# mMicroSD.net
KiCad netlist of a schematic drawn in EAGLE
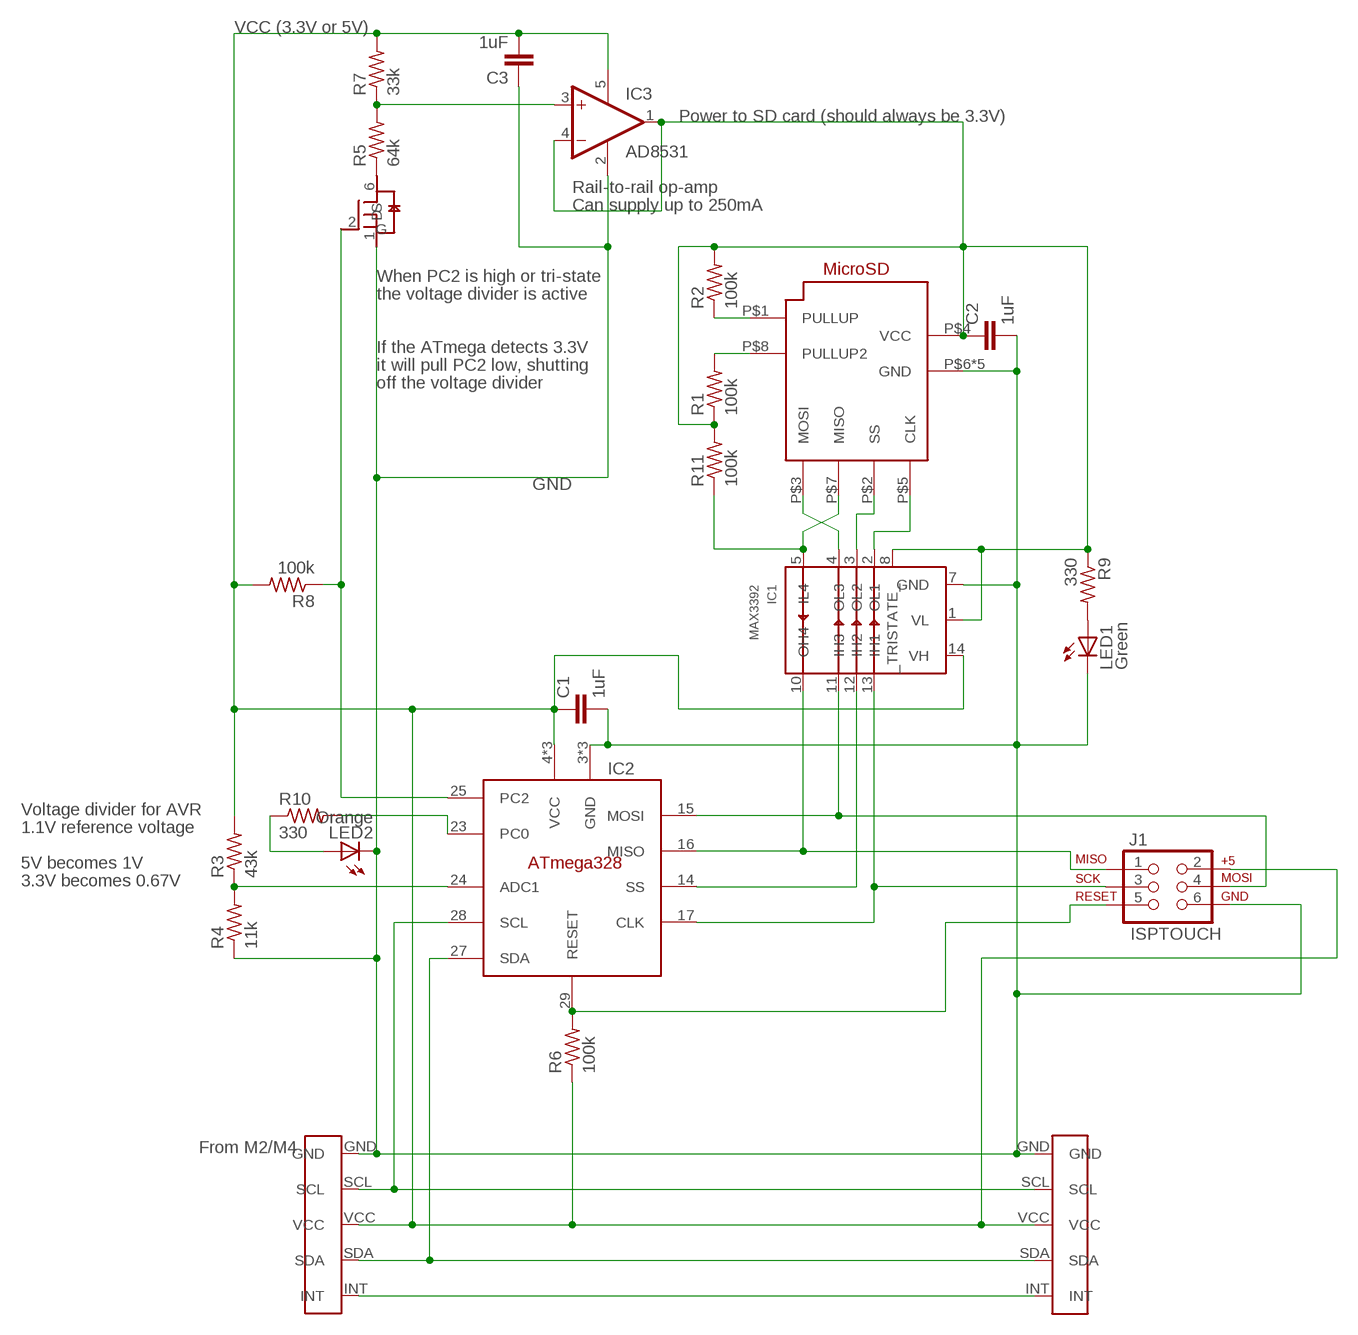
[diagram p0: schematic, sheet 1]

(export (version "E")
  (design (tool "Eeschema 10.0.6"))
  (components
    (comp (ref "C1")
      (value "1uF")
      (footprint "eagle-import:C0603")
      (libsource (lib "eagle-import") (part "C-EUC0603"))
    )
    (comp (ref "C2")
      (value "1uF")
      (footprint "eagle-import:C0603")
      (libsource (lib "eagle-import") (part "C-EUC0603"))
    )
    (comp (ref "C3")
      (value "1uF")
      (footprint "eagle-import:C0603")
      (libsource (lib "eagle-import") (part "C-EUC0603"))
    )
    (comp (ref "IC1")
      (value "MAX3392")
      (footprint "eagle-import:14-TSSOP")
      (libsource (lib "eagle-import") (part "MAX3392"))
    )
    (comp (ref "IC2")
      (value "ATMEGA328")
      (footprint "eagle-import:ATMEGA328")
      (libsource (lib "eagle-import") (part "ATMEGA328"))
    )
    (comp (ref "IC3")
      (value "AD8531")
      (footprint "eagle-import:SOT-23-5")
      (libsource (lib "eagle-import") (part "AD8531"))
    )
    (comp (ref "J1")
      (value "ISPTOUCH")
      (footprint "eagle-import:AVX_9188_6-WAY_SMT")
      (libsource (lib "eagle-import") (part "ISPTOUCH_ADAPTER"))
    )
    (comp (ref "LED1")
      (value "Green")
      (footprint "eagle-import:SML0603")
      (libsource (lib "eagle-import") (part "LEDSML0603"))
    )
    (comp (ref "LED2")
      (value "Orange")
      (footprint "eagle-import:SML0603")
      (libsource (lib "eagle-import") (part "LEDSML0603"))
    )
    (comp (ref "M1")
      (value "NTJD5121N")
      (footprint "eagle-import:SOT-363")
      (libsource (lib "eagle-import") (part "NTJD5121NT1G"))
    )
    (comp (ref "R1")
      (value "100k")
      (footprint "eagle-import:R0603")
      (libsource (lib "eagle-import") (part "R-US_R0603"))
    )
    (comp (ref "R2")
      (value "100k")
      (footprint "eagle-import:R0603")
      (libsource (lib "eagle-import") (part "R-US_R0603"))
    )
    (comp (ref "R3")
      (value "43k")
      (footprint "eagle-import:R0603")
      (libsource (lib "eagle-import") (part "R-US_R0603"))
    )
    (comp (ref "R4")
      (value "11k")
      (footprint "eagle-import:R0603")
      (libsource (lib "eagle-import") (part "R-US_R0603"))
    )
    (comp (ref "R5")
      (value "64k")
      (footprint "eagle-import:R0603")
      (libsource (lib "eagle-import") (part "R-US_R0603"))
    )
    (comp (ref "R6")
      (value "100k")
      (footprint "eagle-import:R0603")
      (libsource (lib "eagle-import") (part "R-US_R0603"))
    )
    (comp (ref "R7")
      (value "33k")
      (footprint "eagle-import:R0603")
      (libsource (lib "eagle-import") (part "R-US_R0603"))
    )
    (comp (ref "R8")
      (value "100k")
      (footprint "eagle-import:R0603")
      (libsource (lib "eagle-import") (part "R-US_R0603"))
    )
    (comp (ref "R9")
      (value "330")
      (footprint "eagle-import:R0603")
      (libsource (lib "eagle-import") (part "R-US_R0603"))
    )
    (comp (ref "R10")
      (value "330")
      (footprint "eagle-import:R0603")
      (libsource (lib "eagle-import") (part "R-US_R0603"))
    )
    (comp (ref "R11")
      (value "100k")
      (footprint "eagle-import:R0603")
      (libsource (lib "eagle-import") (part "R-US_R0603"))
    )
    (comp (ref "SDCONN")
      (value "101-00660-68-6")
      (footprint "eagle-import:101-00660-68-6")
      (libsource (lib "eagle-import") (part "101-00660-68-6"))
    )
    (comp (ref "U$1")
      (value "MBUS_OUT")
      (footprint "eagle-import:MBUS_OUT")
      (libsource (lib "eagle-import") (part "MBUS_OUT"))
    )
    (comp (ref "U$2")
      (value "MBUS_IN")
      (footprint "eagle-import:MBUS_IN")
      (libsource (lib "eagle-import") (part "MBUS_IN"))
    )
  )
  (nets
    (net (code "1") (name "/GND") (class "Default")
      (node (ref "C1") (pin "2") (pinfunction "2_2") (pintype "passive"))
      (node (ref "C2") (pin "2") (pinfunction "2_2") (pintype "passive"))
      (node (ref "C3") (pin "1") (pinfunction "1_1") (pintype "passive"))
      (node (ref "IC1") (pin "7") (pinfunction "GND_7") (pintype "power_in"))
      (node (ref "IC2") (pin "21") (pinfunction "GND_21") (pintype "bidirectional"))
      (node (ref "IC2") (pin "3") (pinfunction "GND_3") (pintype "bidirectional"))
      (node (ref "IC2") (pin "5") (pinfunction "GND_5") (pintype "bidirectional"))
      (node (ref "IC3") (pin "2") (pinfunction "V-_2") (pintype "power_in"))
      (node (ref "J1") (pin "6") (pinfunction "6_6") (pintype "passive"))
      (node (ref "LED1") (pin "C") (pinfunction "C_C") (pintype "passive"))
      (node (ref "LED2") (pin "C") (pinfunction "C_C") (pintype "passive"))
      (node (ref "M1") (pin "1") (pinfunction "S_1") (pintype "bidirectional"))
      (node (ref "R4") (pin "1") (pinfunction "1_1") (pintype "passive"))
      (node (ref "SDCONN") (pin "P$10") (pinfunction "GND_P$10") (pintype "bidirectional"))
      (node (ref "SDCONN") (pin "P$11") (pinfunction "GND_P$11") (pintype "bidirectional"))
      (node (ref "SDCONN") (pin "P$12") (pinfunction "GND_P$12") (pintype "bidirectional"))
      (node (ref "SDCONN") (pin "P$6") (pinfunction "GND_P$6") (pintype "bidirectional"))
      (node (ref "SDCONN") (pin "P$9") (pinfunction "GND_P$9") (pintype "bidirectional"))
      (node (ref "U$1") (pin "GND") (pinfunction "GND_GND") (pintype "bidirectional"))
      (node (ref "U$2") (pin "GND") (pinfunction "GND_GND") (pintype "bidirectional"))
    )
    (net (code "2") (name "Net-(IC1-IH1)") (class "Default")
      (node (ref "IC1") (pin "13") (pinfunction "IH1_13") (pintype "input"))
      (node (ref "IC2") (pin "17") (pinfunction "CLK_17") (pintype "bidirectional"))
      (node (ref "J1") (pin "3") (pinfunction "3_3") (pintype "passive"))
    )
    (net (code "3") (name "Net-(IC1-IH2)") (class "Default")
      (node (ref "IC1") (pin "12") (pinfunction "IH2_12") (pintype "input"))
      (node (ref "IC2") (pin "14") (pinfunction "SS_14") (pintype "bidirectional"))
    )
    (net (code "4") (name "Net-(IC1-IH3)") (class "Default")
      (node (ref "IC1") (pin "11") (pinfunction "IH3_11") (pintype "input"))
      (node (ref "IC2") (pin "15") (pinfunction "MOSI_15") (pintype "bidirectional"))
      (node (ref "J1") (pin "4") (pinfunction "4_4") (pintype "passive"))
    )
    (net (code "5") (name "Net-(IC1-IL4)") (class "Default")
      (node (ref "IC1") (pin "5") (pinfunction "IL4_5") (pintype "input"))
      (node (ref "R11") (pin "1") (pinfunction "1_1") (pintype "passive"))
      (node (ref "SDCONN") (pin "P$7") (pinfunction "MISO_P$7") (pintype "bidirectional"))
    )
    (net (code "6") (name "Net-(IC1-OH4)") (class "Default")
      (node (ref "IC1") (pin "10") (pinfunction "OH4_10") (pintype "output"))
      (node (ref "IC2") (pin "16") (pinfunction "MISO_16") (pintype "bidirectional"))
      (node (ref "J1") (pin "1") (pinfunction "1_1") (pintype "passive"))
    )
    (net (code "7") (name "Net-(IC1-OL1)") (class "Default")
      (node (ref "IC1") (pin "2") (pinfunction "OL1_2") (pintype "output"))
      (node (ref "SDCONN") (pin "P$5") (pinfunction "CLK_P$5") (pintype "bidirectional"))
    )
    (net (code "8") (name "Net-(IC1-OL2)") (class "Default")
      (node (ref "IC1") (pin "3") (pinfunction "OL2_3") (pintype "output"))
      (node (ref "SDCONN") (pin "P$2") (pinfunction "SS_P$2") (pintype "bidirectional"))
    )
    (net (code "9") (name "Net-(IC1-OL3)") (class "Default")
      (node (ref "IC1") (pin "4") (pinfunction "OL3_4") (pintype "output"))
      (node (ref "SDCONN") (pin "P$3") (pinfunction "MOSI_P$3") (pintype "bidirectional"))
    )
    (net (code "10") (name "Net-(IC1-VH)") (class "Default")
      (node (ref "C1") (pin "1") (pinfunction "1_1") (pintype "passive"))
      (node (ref "C3") (pin "2") (pinfunction "2_2") (pintype "passive"))
      (node (ref "IC1") (pin "14") (pinfunction "VH_14") (pintype "power_in"))
      (node (ref "IC2") (pin "18") (pinfunction "VCC_18") (pintype "bidirectional"))
      (node (ref "IC2") (pin "4") (pinfunction "VCC_4") (pintype "bidirectional"))
      (node (ref "IC2") (pin "6") (pinfunction "VCC_6") (pintype "bidirectional"))
      (node (ref "IC3") (pin "5") (pinfunction "V+_5") (pintype "power_in"))
      (node (ref "J1") (pin "2") (pinfunction "2_2") (pintype "passive"))
      (node (ref "R3") (pin "2") (pinfunction "2_2") (pintype "passive"))
      (node (ref "R6") (pin "1") (pinfunction "1_1") (pintype "passive"))
      (node (ref "R7") (pin "2") (pinfunction "2_2") (pintype "passive"))
      (node (ref "R8") (pin "2") (pinfunction "2_2") (pintype "passive"))
      (node (ref "U$1") (pin "VCC") (pinfunction "VCC_VCC") (pintype "bidirectional"))
      (node (ref "U$2") (pin "VCC") (pinfunction "VCC_VCC") (pintype "bidirectional"))
    )
    (net (code "11") (name "Net-(IC1-VL)") (class "Default")
      (node (ref "C2") (pin "1") (pinfunction "1_1") (pintype "passive"))
      (node (ref "IC1") (pin "1") (pinfunction "VL_1") (pintype "power_in"))
      (node (ref "IC1") (pin "8") (pinfunction "_TRISTATE__8") (pintype "input"))
      (node (ref "IC3") (pin "1") (pinfunction "OUT_1") (pintype "output"))
      (node (ref "IC3") (pin "4") (pinfunction "-IN_4") (pintype "input"))
      (node (ref "R1") (pin "1") (pinfunction "1_1") (pintype "passive"))
      (node (ref "R11") (pin "2") (pinfunction "2_2") (pintype "passive"))
      (node (ref "R2") (pin "2") (pinfunction "2_2") (pintype "passive"))
      (node (ref "R9") (pin "1") (pinfunction "1_1") (pintype "passive"))
      (node (ref "SDCONN") (pin "P$4") (pinfunction "VCC_P$4") (pintype "bidirectional"))
    )
    (net (code "12") (name "Net-(IC2-ADC1)") (class "Default")
      (node (ref "IC2") (pin "24") (pinfunction "ADC1_24") (pintype "bidirectional"))
      (node (ref "R3") (pin "1") (pinfunction "1_1") (pintype "passive"))
      (node (ref "R4") (pin "2") (pinfunction "2_2") (pintype "passive"))
    )
    (net (code "13") (name "Net-(IC2-PC0)") (class "Default")
      (node (ref "IC2") (pin "23") (pinfunction "PC0_23") (pintype "bidirectional"))
      (node (ref "R10") (pin "2") (pinfunction "2_2") (pintype "passive"))
    )
    (net (code "14") (name "Net-(IC2-PC2)") (class "Default")
      (node (ref "IC2") (pin "25") (pinfunction "PC2_25") (pintype "bidirectional"))
      (node (ref "M1") (pin "2") (pinfunction "G_2") (pintype "bidirectional"))
      (node (ref "R8") (pin "1") (pinfunction "1_1") (pintype "passive"))
    )
    (net (code "15") (name "Net-(IC2-RESET)") (class "Default")
      (node (ref "IC2") (pin "29") (pinfunction "RESET_29") (pintype "bidirectional"))
      (node (ref "J1") (pin "5") (pinfunction "5_5") (pintype "passive"))
      (node (ref "R6") (pin "2") (pinfunction "2_2") (pintype "passive"))
    )
    (net (code "16") (name "Net-(IC2-SCL)") (class "Default")
      (node (ref "IC2") (pin "28") (pinfunction "SCL_28") (pintype "bidirectional"))
      (node (ref "U$1") (pin "SCL") (pinfunction "SCL_SCL") (pintype "bidirectional"))
      (node (ref "U$2") (pin "SCL") (pinfunction "SCL_SCL") (pintype "bidirectional"))
    )
    (net (code "17") (name "Net-(IC2-SDA)") (class "Default")
      (node (ref "IC2") (pin "27") (pinfunction "SDA_27") (pintype "bidirectional"))
      (node (ref "U$1") (pin "SDA") (pinfunction "SDA_SDA") (pintype "bidirectional"))
      (node (ref "U$2") (pin "SDA") (pinfunction "SDA_SDA") (pintype "bidirectional"))
    )
    (net (code "18") (name "Net-(IC3-+IN)") (class "Default")
      (node (ref "IC3") (pin "3") (pinfunction "+IN_3") (pintype "input"))
      (node (ref "R5") (pin "2") (pinfunction "2_2") (pintype "passive"))
      (node (ref "R7") (pin "1") (pinfunction "1_1") (pintype "passive"))
    )
    (net (code "19") (name "Net-(LED1-PadA)") (class "Default")
      (node (ref "LED1") (pin "A") (pinfunction "A_A") (pintype "passive"))
      (node (ref "R9") (pin "2") (pinfunction "2_2") (pintype "passive"))
    )
    (net (code "20") (name "Net-(LED2-PadA)") (class "Default")
      (node (ref "LED2") (pin "A") (pinfunction "A_A") (pintype "passive"))
      (node (ref "R10") (pin "1") (pinfunction "1_1") (pintype "passive"))
    )
    (net (code "21") (name "Net-(M1A-D)") (class "Default")
      (node (ref "M1") (pin "6") (pinfunction "D_6") (pintype "bidirectional"))
      (node (ref "R5") (pin "1") (pinfunction "1_1") (pintype "passive"))
    )
    (net (code "22") (name "Net-(SDCONN-PULLUP)") (class "Default")
      (node (ref "R2") (pin "1") (pinfunction "1_1") (pintype "passive"))
      (node (ref "SDCONN") (pin "P$1") (pinfunction "PULLUP_P$1") (pintype "bidirectional"))
    )
    (net (code "23") (name "Net-(SDCONN-PULLUP2)") (class "Default")
      (node (ref "R1") (pin "2") (pinfunction "2_2") (pintype "passive"))
      (node (ref "SDCONN") (pin "P$8") (pinfunction "PULLUP2_P$8") (pintype "bidirectional"))
    )
    (net (code "24") (name "Net-(U$1-PadINT)") (class "Default")
      (node (ref "U$1") (pin "INT") (pinfunction "INT_INT") (pintype "bidirectional"))
      (node (ref "U$2") (pin "INT") (pinfunction "INT_INT") (pintype "bidirectional"))
    )
  )
)
